# 4-bit-module.net
KiCad netlist of a schematic drawn in EAGLE
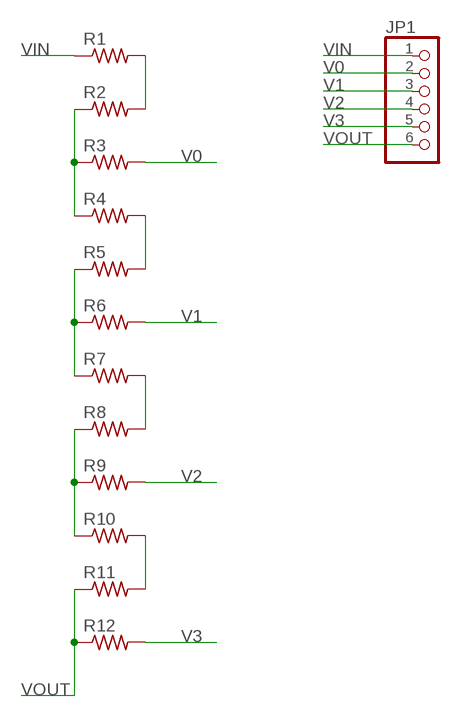
[diagram p0: schematic, sheet 1]

(export (version "E")
  (design (tool "Eeschema 10.0.6"))
  (components
    (comp (ref "JP1")
      (value "PINHD-1X6/90")
      (footprint "eagle-import:1X06_90")
      (libsource (lib "eagle-import") (part "PINHD-1X6/90"))
    )
    (comp (ref "R1")
      (value "R-US_0204/7")
      (footprint "eagle-import:0204_7")
      (libsource (lib "eagle-import") (part "R-US_0204/7"))
    )
    (comp (ref "R2")
      (value "R-US_0204/7")
      (footprint "eagle-import:0204_7")
      (libsource (lib "eagle-import") (part "R-US_0204/7"))
    )
    (comp (ref "R3")
      (value "R-US_0204/7")
      (footprint "eagle-import:0204_7")
      (libsource (lib "eagle-import") (part "R-US_0204/7"))
    )
    (comp (ref "R4")
      (value "R-US_0204/7")
      (footprint "eagle-import:0204_7")
      (libsource (lib "eagle-import") (part "R-US_0204/7"))
    )
    (comp (ref "R5")
      (value "R-US_0204/7")
      (footprint "eagle-import:0204_7")
      (libsource (lib "eagle-import") (part "R-US_0204/7"))
    )
    (comp (ref "R6")
      (value "R-US_0204/7")
      (footprint "eagle-import:0204_7")
      (libsource (lib "eagle-import") (part "R-US_0204/7"))
    )
    (comp (ref "R7")
      (value "R-US_0204/7")
      (footprint "eagle-import:0204_7")
      (libsource (lib "eagle-import") (part "R-US_0204/7"))
    )
    (comp (ref "R8")
      (value "R-US_0204/7")
      (footprint "eagle-import:0204_7")
      (libsource (lib "eagle-import") (part "R-US_0204/7"))
    )
    (comp (ref "R9")
      (value "R-US_0204/7")
      (footprint "eagle-import:0204_7")
      (libsource (lib "eagle-import") (part "R-US_0204/7"))
    )
    (comp (ref "R10")
      (value "R-US_0204/7")
      (footprint "eagle-import:0204_7")
      (libsource (lib "eagle-import") (part "R-US_0204/7"))
    )
    (comp (ref "R11")
      (value "R-US_0204/7")
      (footprint "eagle-import:0204_7")
      (libsource (lib "eagle-import") (part "R-US_0204/7"))
    )
    (comp (ref "R12")
      (value "R-US_0204/7")
      (footprint "eagle-import:0204_7")
      (libsource (lib "eagle-import") (part "R-US_0204/7"))
    )
  )
  (nets
    (net (code "1") (name "/V0") (class "Default")
      (node (ref "JP1") (pin "2") (pinfunction "2_2") (pintype "passive"))
      (node (ref "R3") (pin "2") (pinfunction "2_2") (pintype "passive"))
    )
    (net (code "2") (name "/V1") (class "Default")
      (node (ref "JP1") (pin "3") (pinfunction "3_3") (pintype "passive"))
      (node (ref "R6") (pin "2") (pinfunction "2_2") (pintype "passive"))
    )
    (net (code "3") (name "/V2") (class "Default")
      (node (ref "JP1") (pin "4") (pinfunction "4_4") (pintype "passive"))
      (node (ref "R9") (pin "2") (pinfunction "2_2") (pintype "passive"))
    )
    (net (code "4") (name "/V3") (class "Default")
      (node (ref "JP1") (pin "5") (pinfunction "5_5") (pintype "passive"))
      (node (ref "R12") (pin "2") (pinfunction "2_2") (pintype "passive"))
    )
    (net (code "5") (name "/VIN") (class "Default")
      (node (ref "JP1") (pin "1") (pinfunction "1_1") (pintype "passive"))
      (node (ref "R1") (pin "1") (pinfunction "1_1") (pintype "passive"))
    )
    (net (code "6") (name "/VOUT") (class "Default")
      (node (ref "JP1") (pin "6") (pinfunction "6_6") (pintype "passive"))
      (node (ref "R11") (pin "1") (pinfunction "1_1") (pintype "passive"))
      (node (ref "R12") (pin "1") (pinfunction "1_1") (pintype "passive"))
    )
    (net (code "7") (name "Net-(R1-Pad2)") (class "Default")
      (node (ref "R1") (pin "2") (pinfunction "2_2") (pintype "passive"))
      (node (ref "R2") (pin "2") (pinfunction "2_2") (pintype "passive"))
    )
    (net (code "8") (name "Net-(R2-Pad1)") (class "Default")
      (node (ref "R2") (pin "1") (pinfunction "1_1") (pintype "passive"))
      (node (ref "R3") (pin "1") (pinfunction "1_1") (pintype "passive"))
      (node (ref "R4") (pin "1") (pinfunction "1_1") (pintype "passive"))
    )
    (net (code "9") (name "Net-(R4-Pad2)") (class "Default")
      (node (ref "R4") (pin "2") (pinfunction "2_2") (pintype "passive"))
      (node (ref "R5") (pin "2") (pinfunction "2_2") (pintype "passive"))
    )
    (net (code "10") (name "Net-(R5-Pad1)") (class "Default")
      (node (ref "R5") (pin "1") (pinfunction "1_1") (pintype "passive"))
      (node (ref "R6") (pin "1") (pinfunction "1_1") (pintype "passive"))
      (node (ref "R7") (pin "1") (pinfunction "1_1") (pintype "passive"))
    )
    (net (code "11") (name "Net-(R7-Pad2)") (class "Default")
      (node (ref "R7") (pin "2") (pinfunction "2_2") (pintype "passive"))
      (node (ref "R8") (pin "2") (pinfunction "2_2") (pintype "passive"))
    )
    (net (code "12") (name "Net-(R10-Pad1)") (class "Default")
      (node (ref "R10") (pin "1") (pinfunction "1_1") (pintype "passive"))
      (node (ref "R8") (pin "1") (pinfunction "1_1") (pintype "passive"))
      (node (ref "R9") (pin "1") (pinfunction "1_1") (pintype "passive"))
    )
    (net (code "13") (name "Net-(R10-Pad2)") (class "Default")
      (node (ref "R10") (pin "2") (pinfunction "2_2") (pintype "passive"))
      (node (ref "R11") (pin "2") (pinfunction "2_2") (pintype "passive"))
    )
  )
)
